# main.net
KiCad netlist of a schematic drawn in EAGLE
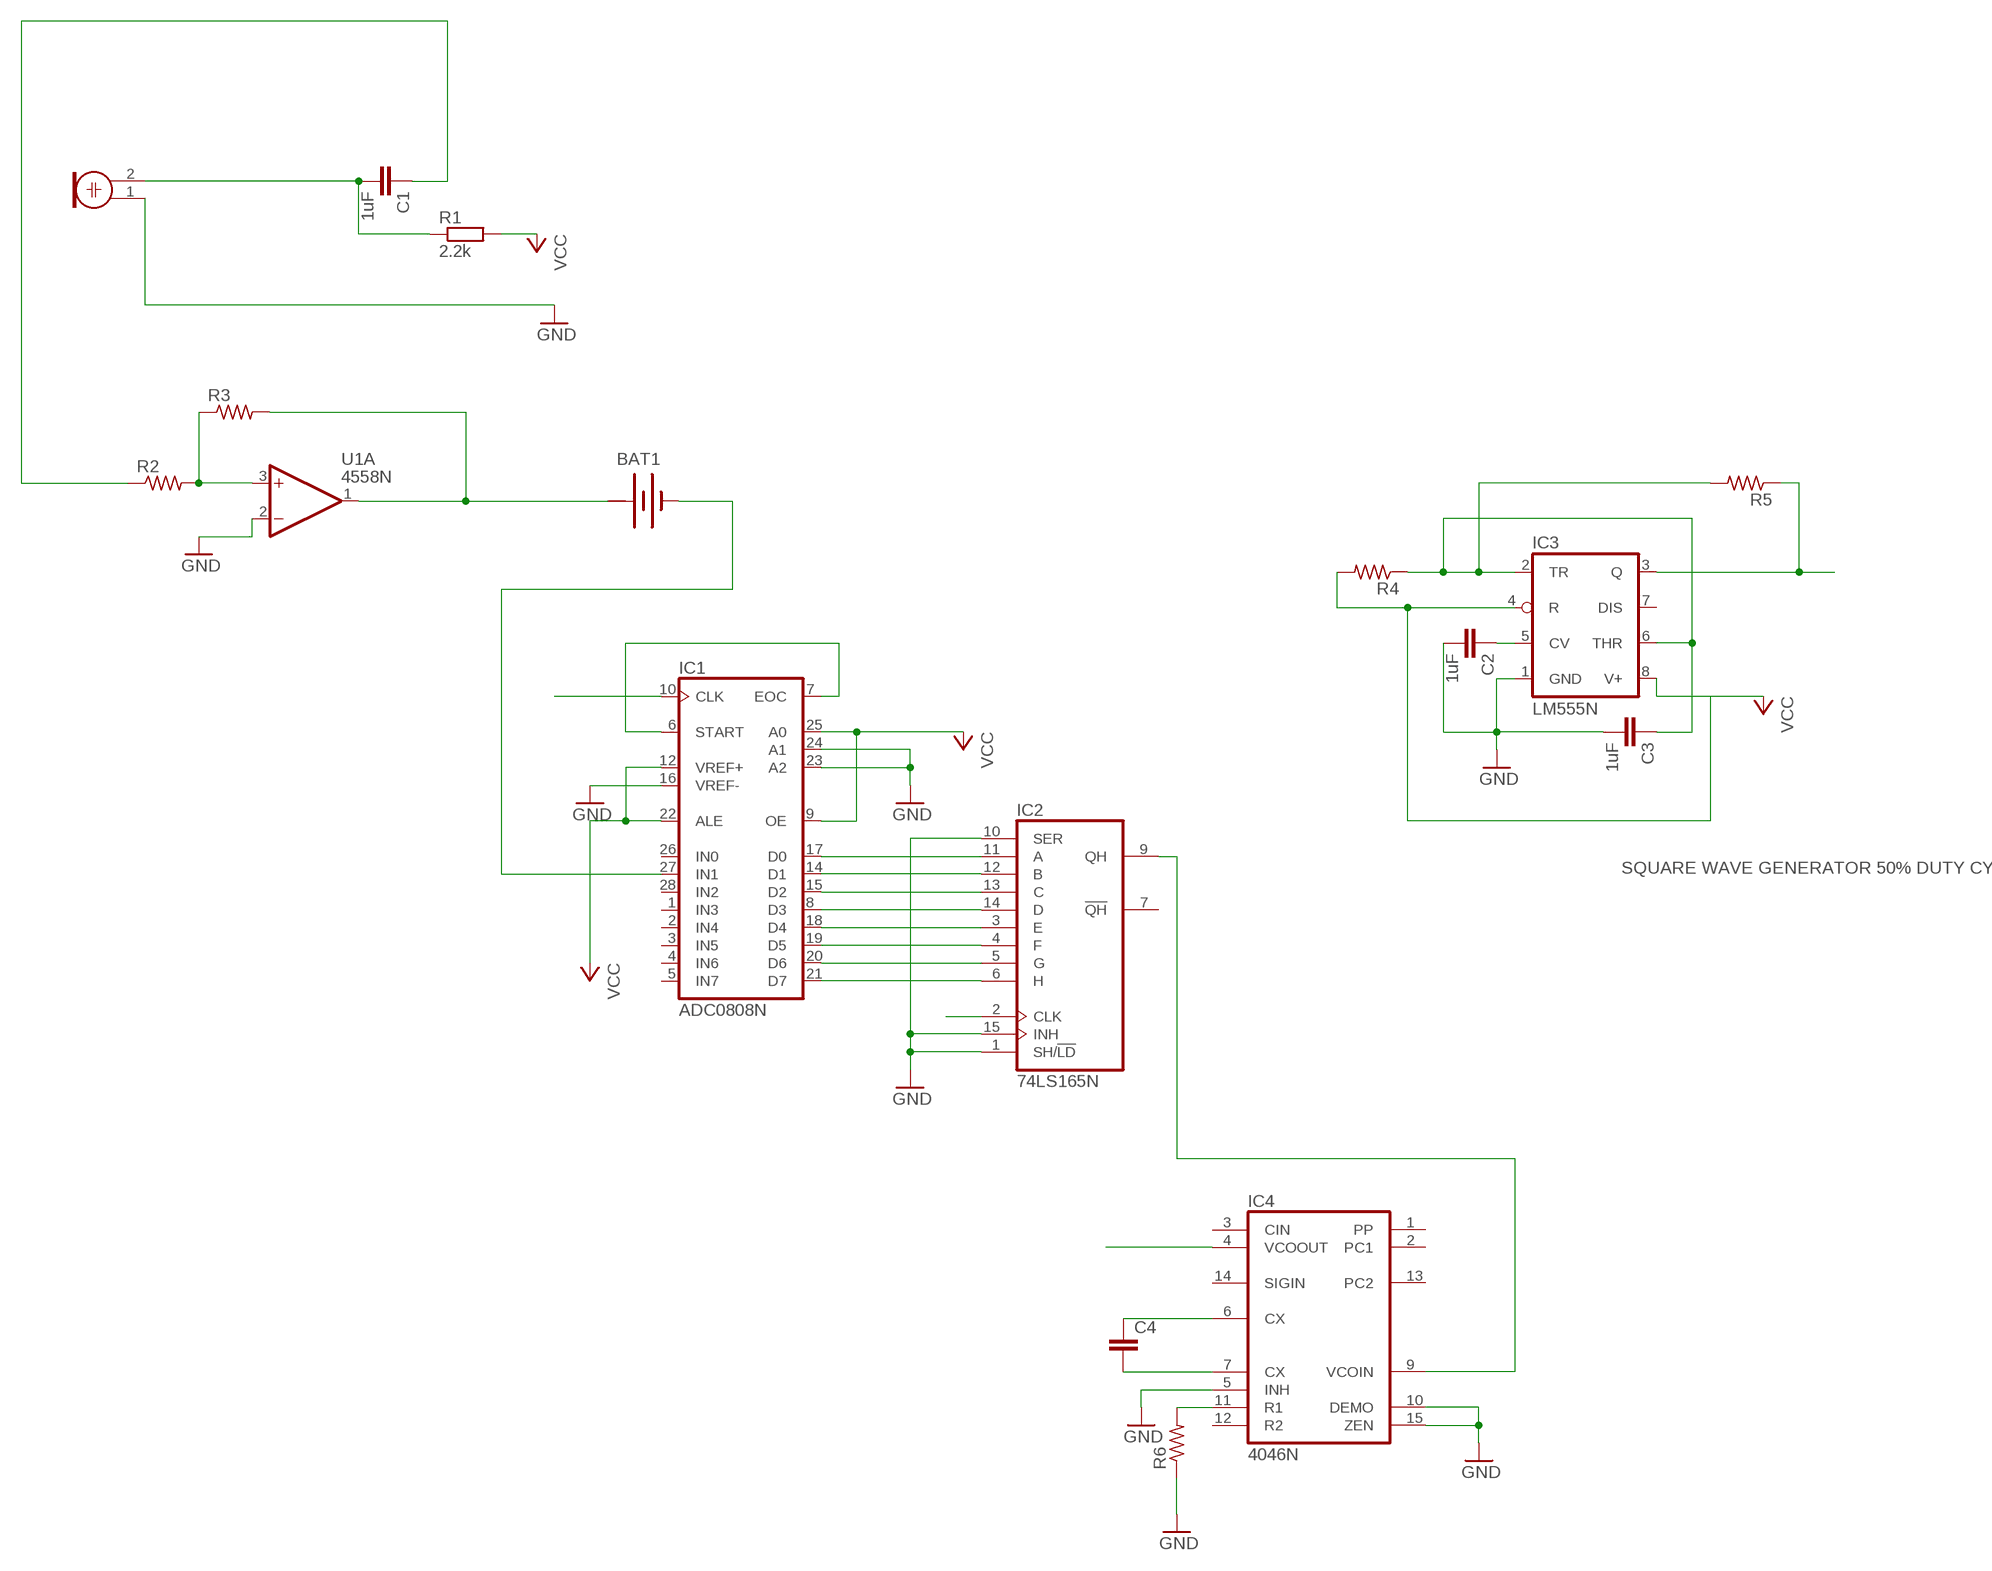
[diagram p0: schematic, sheet 1]

(export (version "E")
  (design (tool "Eeschema 10.0.6"))
  (components
    (comp (ref "BAT1")
      (value "BATTERY")
      (footprint "eagle-import:BATTERY")
      (libsource (lib "eagle-import") (part "BATTERY"))
    )
    (comp (ref "C1")
      (value "1uF")
      (footprint "eagle-import:C2.5-3")
      (libsource (lib "eagle-import") (part "C2,5-3"))
    )
    (comp (ref "C2")
      (value "1uF")
      (footprint "eagle-import:C2.5-3")
      (libsource (lib "eagle-import") (part "C2,5-3"))
    )
    (comp (ref "C3")
      (value "1uF")
      (footprint "eagle-import:C2.5-3")
      (libsource (lib "eagle-import") (part "C2,5-3"))
    )
    (comp (ref "C4")
      (value "C2.5/2")
      (footprint "eagle-import:C2.5-2")
      (libsource (lib "eagle-import") (part "C2.5/2"))
    )
    (comp (ref "IC1")
      (value "ADC0808N")
      (footprint "eagle-import:DIL28-6")
      (libsource (lib "eagle-import") (part "ADC0808N"))
    )
    (comp (ref "IC2")
      (value "74LS165N")
      (footprint "eagle-import:DIL16")
      (libsource (lib "eagle-import") (part "74165NLS"))
    )
    (comp (ref "IC3")
      (value "LM555N")
      (footprint "eagle-import:DIL08-ROUND")
      (libsource (lib "eagle-import") (part "555NLM"))
    )
    (comp (ref "IC4")
      (value "4046N")
      (footprint "eagle-import:DIL16")
      (libsource (lib "eagle-import") (part "4046N"))
    )
    (comp (ref "M1")
      (value "ELECTRET_MICROPHON-F6050AP")
      (footprint "eagle-import:F6050AP")
      (libsource (lib "eagle-import") (part "ELECTRET_MICROPHON-F6050AP"))
    )
    (comp (ref "R1")
      (value "2.2k")
      (footprint "eagle-import:0204_7")
      (libsource (lib "eagle-import") (part "R-EU_0204/7"))
    )
    (comp (ref "R2")
      (value "R-US_0204/7")
      (footprint "eagle-import:0204_7")
      (libsource (lib "eagle-import") (part "R-US_0204/7"))
    )
    (comp (ref "R3")
      (value "R-US_0204/7")
      (footprint "eagle-import:0204_7")
      (libsource (lib "eagle-import") (part "R-US_0204/7"))
    )
    (comp (ref "R4")
      (value "R-US_0204/7")
      (footprint "eagle-import:0204_7")
      (libsource (lib "eagle-import") (part "R-US_0204/7"))
    )
    (comp (ref "R5")
      (value "R-US_0204/7")
      (footprint "eagle-import:0204_7")
      (libsource (lib "eagle-import") (part "R-US_0204/7"))
    )
    (comp (ref "R6")
      (value "R-US_0204/7")
      (footprint "eagle-import:0204_7")
      (libsource (lib "eagle-import") (part "R-US_0204/7"))
    )
    (comp (ref "U1")
      (value "4558N")
      (footprint "eagle-import:DIL08")
      (libsource (lib "eagle-import") (part "4558N"))
    )
  )
  (nets
    (net (code "1") (name "+") (class "Default")
      (node (ref "BAT1") (pin "+@1") (pinfunction "+_+@1") (pintype "power_in"))
    )
    (net (code "2") (name "CLK") (class "Default")
      (node (ref "IC1") (pin "10") (pinfunction "CLK_10") (pintype "input"))
      (node (ref "IC2") (pin "2") (pinfunction "CLK_2") (pintype "input"))
      (node (ref "IC3") (pin "3") (pinfunction "Q_3") (pintype "output"))
      (node (ref "R5") (pin "1") (pinfunction "1_1") (pintype "passive"))
    )
    (net (code "3") (name "GND") (class "Default")
      (node (ref "C2") (pin "2") (pinfunction "2_2") (pintype "passive"))
      (node (ref "C3") (pin "2") (pinfunction "2_2") (pintype "passive"))
      (node (ref "IC1") (pin "16") (pinfunction "VREF-_16") (pintype "input"))
      (node (ref "IC1") (pin "23") (pinfunction "A2_23") (pintype "input"))
      (node (ref "IC1") (pin "24") (pinfunction "A1_24") (pintype "input"))
      (node (ref "IC2") (pin "1") (pinfunction "SH/~{LD}_1") (pintype "input"))
      (node (ref "IC2") (pin "10") (pinfunction "SER_10") (pintype "input"))
      (node (ref "IC2") (pin "15") (pinfunction "INH_15") (pintype "input"))
      (node (ref "IC3") (pin "1") (pinfunction "GND_1") (pintype "power_in"))
      (node (ref "IC4") (pin "10") (pinfunction "DEMO_10") (pintype "output"))
      (node (ref "IC4") (pin "15") (pinfunction "ZEN_15") (pintype "input"))
      (node (ref "IC4") (pin "5") (pinfunction "INH_5") (pintype "input"))
      (node (ref "M1") (pin "1") (pinfunction "1_1") (pintype "passive"))
      (node (ref "R6") (pin "1") (pinfunction "1_1") (pintype "passive"))
      (node (ref "U1") (pin "2") (pinfunction "-IN_2") (pintype "input"))
    )
    (net (code "4") (name "Net-(C1-Pad1)") (class "Default")
      (node (ref "C1") (pin "1") (pinfunction "1_1") (pintype "passive"))
      (node (ref "R2") (pin "1") (pinfunction "1_1") (pintype "passive"))
    )
    (net (code "5") (name "Net-(C1-Pad2)") (class "Default")
      (node (ref "C1") (pin "2") (pinfunction "2_2") (pintype "passive"))
      (node (ref "M1") (pin "2") (pinfunction "2_2") (pintype "passive"))
      (node (ref "R1") (pin "1") (pinfunction "1_1") (pintype "passive"))
    )
    (net (code "6") (name "Net-(C4-Pad1)") (class "Default")
      (node (ref "C4") (pin "1") (pinfunction "1_1") (pintype "passive"))
      (node (ref "IC4") (pin "6") (pinfunction "CX_6") (pintype "input"))
    )
    (net (code "7") (name "Net-(C4-Pad2)") (class "Default")
      (node (ref "C4") (pin "2") (pinfunction "2_2") (pintype "passive"))
      (node (ref "IC4") (pin "7") (pinfunction "CX_7") (pintype "input"))
    )
    (net (code "8") (name "Net-(IC1A-D0)") (class "Default")
      (node (ref "IC1") (pin "17") (pinfunction "D0_17") (pintype "tri_state"))
      (node (ref "IC2") (pin "11") (pinfunction "A_11") (pintype "input"))
    )
    (net (code "9") (name "Net-(IC1A-D1)") (class "Default")
      (node (ref "IC1") (pin "14") (pinfunction "D1_14") (pintype "tri_state"))
      (node (ref "IC2") (pin "12") (pinfunction "B_12") (pintype "input"))
    )
    (net (code "10") (name "Net-(IC1A-D2)") (class "Default")
      (node (ref "IC1") (pin "15") (pinfunction "D2_15") (pintype "tri_state"))
      (node (ref "IC2") (pin "13") (pinfunction "C_13") (pintype "input"))
    )
    (net (code "11") (name "Net-(IC1A-D3)") (class "Default")
      (node (ref "IC1") (pin "8") (pinfunction "D3_8") (pintype "tri_state"))
      (node (ref "IC2") (pin "14") (pinfunction "D_14") (pintype "input"))
    )
    (net (code "12") (name "Net-(IC1A-D4)") (class "Default")
      (node (ref "IC1") (pin "18") (pinfunction "D4_18") (pintype "tri_state"))
      (node (ref "IC2") (pin "3") (pinfunction "E_3") (pintype "input"))
    )
    (net (code "13") (name "Net-(IC1A-D5)") (class "Default")
      (node (ref "IC1") (pin "19") (pinfunction "D5_19") (pintype "tri_state"))
      (node (ref "IC2") (pin "4") (pinfunction "F_4") (pintype "input"))
    )
    (net (code "14") (name "Net-(IC1A-D6)") (class "Default")
      (node (ref "IC1") (pin "20") (pinfunction "D6_20") (pintype "tri_state"))
      (node (ref "IC2") (pin "5") (pinfunction "G_5") (pintype "input"))
    )
    (net (code "15") (name "Net-(IC1A-D7)") (class "Default")
      (node (ref "IC1") (pin "21") (pinfunction "D7_21") (pintype "tri_state"))
      (node (ref "IC2") (pin "6") (pinfunction "H_6") (pintype "input"))
    )
    (net (code "16") (name "Net-(IC1A-EOC)") (class "Default")
      (node (ref "IC1") (pin "6") (pinfunction "START_6") (pintype "input"))
      (node (ref "IC1") (pin "7") (pinfunction "EOC_7") (pintype "output"))
    )
    (net (code "17") (name "Net-(IC1A-IN1)") (class "Default")
      (node (ref "BAT1") (pin "-") (pinfunction "-_-") (pintype "power_in"))
      (node (ref "IC1") (pin "27") (pinfunction "IN1_27") (pintype "input"))
    )
    (net (code "18") (name "Net-(IC2A-QH)") (class "Default")
      (node (ref "IC2") (pin "9") (pinfunction "QH_9") (pintype "output"))
      (node (ref "IC4") (pin "9") (pinfunction "VCOIN_9") (pintype "input"))
    )
    (net (code "19") (name "Net-(IC3-CV)") (class "Default")
      (node (ref "C2") (pin "1") (pinfunction "1_1") (pintype "passive"))
      (node (ref "IC3") (pin "5") (pinfunction "CV_5") (pintype "input"))
    )
    (net (code "20") (name "Net-(IC3-THR)") (class "Default")
      (node (ref "C3") (pin "1") (pinfunction "1_1") (pintype "passive"))
      (node (ref "IC3") (pin "2") (pinfunction "TR_2") (pintype "input"))
      (node (ref "IC3") (pin "6") (pinfunction "THR_6") (pintype "input"))
      (node (ref "R4") (pin "1") (pinfunction "1_1") (pintype "passive"))
      (node (ref "R5") (pin "2") (pinfunction "2_2") (pintype "passive"))
    )
    (net (code "21") (name "Net-(IC4A-R1)") (class "Default")
      (node (ref "IC4") (pin "11") (pinfunction "R1_11") (pintype "input"))
      (node (ref "R6") (pin "2") (pinfunction "2_2") (pintype "passive"))
    )
    (net (code "22") (name "Net-(U1A-+IN)") (class "Default")
      (node (ref "R2") (pin "2") (pinfunction "2_2") (pintype "passive"))
      (node (ref "R3") (pin "1") (pinfunction "1_1") (pintype "passive"))
      (node (ref "U1") (pin "3") (pinfunction "+IN_3") (pintype "input"))
    )
    (net (code "23") (name "Net-(U1A-OUT)") (class "Default")
      (node (ref "BAT1") (pin "+") (pinfunction "+_+") (pintype "power_in"))
      (node (ref "R3") (pin "2") (pinfunction "2_2") (pintype "passive"))
      (node (ref "U1") (pin "1") (pinfunction "OUT_1") (pintype "output"))
    )
    (net (code "24") (name "VCC") (class "Default")
      (node (ref "IC1") (pin "12") (pinfunction "VREF+_12") (pintype "input"))
      (node (ref "IC1") (pin "22") (pinfunction "ALE_22") (pintype "input"))
      (node (ref "IC1") (pin "25") (pinfunction "A0_25") (pintype "input"))
      (node (ref "IC1") (pin "9") (pinfunction "OE_9") (pintype "input"))
      (node (ref "IC3") (pin "4") (pinfunction "R_4") (pintype "input"))
      (node (ref "IC3") (pin "8") (pinfunction "V+_8") (pintype "power_in"))
      (node (ref "R1") (pin "2") (pinfunction "2_2") (pintype "passive"))
      (node (ref "R4") (pin "2") (pinfunction "2_2") (pintype "passive"))
    )
    (net (code "25") (name "unconnected-(IC1A-IN0-Pad26)") (class "Default")
      (node (ref "IC1") (pin "26") (pinfunction "IN0_26") (pintype "input"))
    )
    (net (code "26") (name "unconnected-(IC1A-IN2-Pad28)") (class "Default")
      (node (ref "IC1") (pin "28") (pinfunction "IN2_28") (pintype "input"))
    )
    (net (code "27") (name "unconnected-(IC1A-IN3-Pad1)") (class "Default")
      (node (ref "IC1") (pin "1") (pinfunction "IN3_1") (pintype "input"))
    )
    (net (code "28") (name "unconnected-(IC1A-IN4-Pad2)") (class "Default")
      (node (ref "IC1") (pin "2") (pinfunction "IN4_2") (pintype "input"))
    )
    (net (code "29") (name "unconnected-(IC1A-IN5-Pad3)") (class "Default")
      (node (ref "IC1") (pin "3") (pinfunction "IN5_3") (pintype "input"))
    )
    (net (code "30") (name "unconnected-(IC1A-IN6-Pad4)") (class "Default")
      (node (ref "IC1") (pin "4") (pinfunction "IN6_4") (pintype "input"))
    )
    (net (code "31") (name "unconnected-(IC1A-IN7-Pad5)") (class "Default")
      (node (ref "IC1") (pin "5") (pinfunction "IN7_5") (pintype "input"))
    )
    (net (code "32") (name "unconnected-(IC2A-~{QH}-Pad7)") (class "Default")
      (node (ref "IC2") (pin "7") (pinfunction "~{QH}_7") (pintype "output"))
    )
    (net (code "33") (name "unconnected-(IC3-DIS-Pad7)") (class "Default")
      (node (ref "IC3") (pin "7") (pinfunction "DIS_7") (pintype "input"))
    )
    (net (code "34") (name "unconnected-(IC4A-CIN-Pad3)") (class "Default")
      (node (ref "IC4") (pin "3") (pinfunction "CIN_3") (pintype "input"))
    )
    (net (code "35") (name "unconnected-(IC4A-PC1-Pad2)") (class "Default")
      (node (ref "IC4") (pin "2") (pinfunction "PC1_2") (pintype "output"))
    )
    (net (code "36") (name "unconnected-(IC4A-PC2-Pad13)") (class "Default")
      (node (ref "IC4") (pin "13") (pinfunction "PC2_13") (pintype "output"))
    )
    (net (code "37") (name "unconnected-(IC4A-PP-Pad1)") (class "Default")
      (node (ref "IC4") (pin "1") (pinfunction "PP_1") (pintype "output"))
    )
    (net (code "38") (name "unconnected-(IC4A-R2-Pad12)") (class "Default")
      (node (ref "IC4") (pin "12") (pinfunction "R2_12") (pintype "input"))
    )
    (net (code "39") (name "unconnected-(IC4A-SIGIN-Pad14)") (class "Default")
      (node (ref "IC4") (pin "14") (pinfunction "SIGIN_14") (pintype "input"))
    )
    (net (code "40") (name "unconnected-(IC4A-VCOOUT-Pad4)") (class "Default")
      (node (ref "IC4") (pin "4") (pinfunction "VCOOUT_4") (pintype "output"))
    )
  )
)
